# os20_oldenc.net
KiCad netlist of a schematic drawn in EAGLE
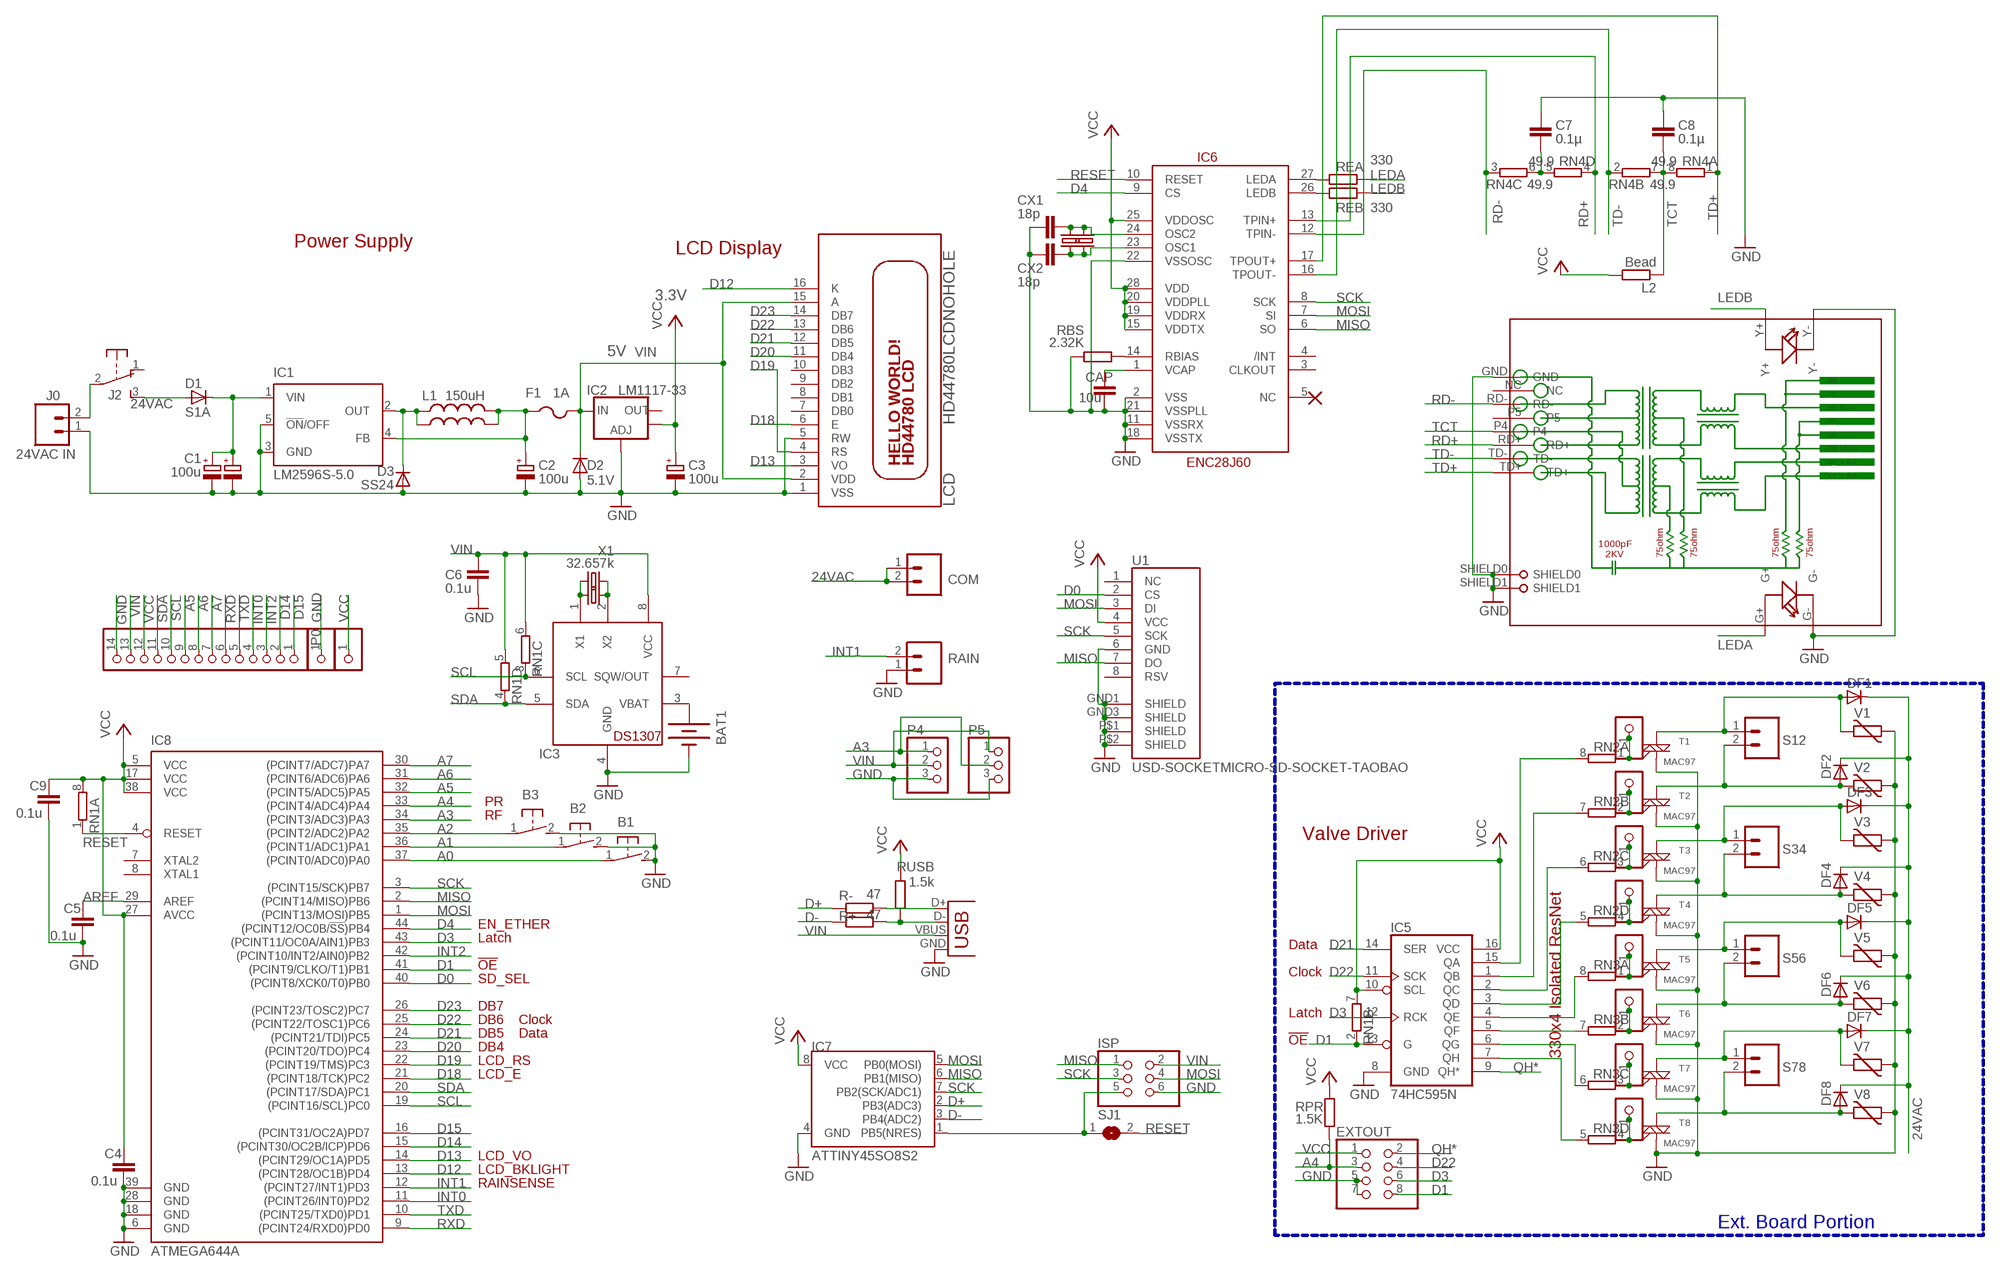
[diagram p0: schematic, sheet 1]

(export (version "E")
  (design (tool "Eeschema 10.0.6"))
  (components
    (comp (ref "B1")
      (value "31-XX")
      (footprint "eagle-import:B3F-31XX")
      (libsource (lib "eagle-import") (part "31-XX"))
    )
    (comp (ref "B2")
      (value "31-XX")
      (footprint "eagle-import:B3F-31XX")
      (libsource (lib "eagle-import") (part "31-XX"))
    )
    (comp (ref "B3")
      (value "31-XX")
      (footprint "eagle-import:B3F-31XX")
      (libsource (lib "eagle-import") (part "31-XX"))
    )
    (comp (ref "BAT1")
      (value "BATTERYBATTERY_12MM_SMT")
      (footprint "eagle-import:BATTCON_12MM_SMT")
      (libsource (lib "eagle-import") (part "BATTERYBATTERY_12MM_SMT"))
    )
    (comp (ref "C1")
      (value "100u")
      (footprint "eagle-import:E3,5-8")
      (libsource (lib "eagle-import") (part "CPOL-EUE3.5-8"))
    )
    (comp (ref "C1'")
      (value "100u")
      (footprint "eagle-import:PANASONIC_E")
      (libsource (lib "eagle-import") (part "CPOL-EUE"))
    )
    (comp (ref "C2")
      (value "100u")
      (footprint "eagle-import:PANASONIC_D")
      (libsource (lib "eagle-import") (part "CPOL-EUD"))
    )
    (comp (ref "C3")
      (value "100u")
      (footprint "eagle-import:PANASONIC_D")
      (libsource (lib "eagle-import") (part "CPOL-EUD"))
    )
    (comp (ref "C4")
      (value "0.1u")
      (footprint "eagle-import:C0805")
      (libsource (lib "eagle-import") (part "C-EUC0805"))
    )
    (comp (ref "C5")
      (value "0.1u")
      (footprint "eagle-import:C0805")
      (libsource (lib "eagle-import") (part "C-EUC0805"))
    )
    (comp (ref "C6")
      (value "0.1u")
      (footprint "eagle-import:C0805")
      (libsource (lib "eagle-import") (part "C-EUC0805"))
    )
    (comp (ref "C7")
      (value "0.1µ")
      (footprint "eagle-import:C0805")
      (libsource (lib "eagle-import") (part "resistor_C-EUC0805"))
    )
    (comp (ref "C8")
      (value "0.1µ")
      (footprint "eagle-import:C0805")
      (libsource (lib "eagle-import") (part "resistor_C-EUC0805"))
    )
    (comp (ref "C9")
      (value "0.1u")
      (footprint "eagle-import:C0805")
      (libsource (lib "eagle-import") (part "C-EUC0805"))
    )
    (comp (ref "CAP")
      (value "10u")
      (footprint "eagle-import:C0805")
      (libsource (lib "eagle-import") (part "resistor_C-EUC0805"))
    )
    (comp (ref "COM")
      (value "M025MM")
      (footprint "eagle-import:SCREWTERMINAL-5MM-2")
      (libsource (lib "eagle-import") (part "M025MM"))
    )
    (comp (ref "CX1")
      (value "18p")
      (footprint "eagle-import:C0805")
      (libsource (lib "eagle-import") (part "resistor_C-EUC0805"))
    )
    (comp (ref "CX2")
      (value "18p")
      (footprint "eagle-import:C0805")
      (libsource (lib "eagle-import") (part "resistor_C-EUC0805"))
    )
    (comp (ref "D1")
      (value "S1A")
      (footprint "eagle-import:DO-214AC")
      (libsource (lib "eagle-import") (part "DIODE-DO-214AC"))
    )
    (comp (ref "D2")
      (value "5.1V")
      (footprint "eagle-import:MINIMELF")
      (libsource (lib "eagle-import") (part "DIODE-MINIMELF"))
    )
    (comp (ref "D3")
      (value "SS24")
      (footprint "eagle-import:DO-214AC")
      (libsource (lib "eagle-import") (part "DIODE-DO-214AC"))
    )
    (comp (ref "DF1")
      (value "DIODE-D-2.5")
      (footprint "eagle-import:D-2.5")
      (libsource (lib "eagle-import") (part "DIODE-D-2.5"))
    )
    (comp (ref "DF2")
      (value "DIODE-D-2.5")
      (footprint "eagle-import:D-2.5")
      (libsource (lib "eagle-import") (part "DIODE-D-2.5"))
    )
    (comp (ref "DF3")
      (value "DIODE-D-2.5")
      (footprint "eagle-import:D-2.5")
      (libsource (lib "eagle-import") (part "DIODE-D-2.5"))
    )
    (comp (ref "DF4")
      (value "DIODE-D-2.5")
      (footprint "eagle-import:D-2.5")
      (libsource (lib "eagle-import") (part "DIODE-D-2.5"))
    )
    (comp (ref "DF5")
      (value "DIODE-D-2.5")
      (footprint "eagle-import:D-2.5")
      (libsource (lib "eagle-import") (part "DIODE-D-2.5"))
    )
    (comp (ref "DF6")
      (value "DIODE-D-2.5")
      (footprint "eagle-import:D-2.5")
      (libsource (lib "eagle-import") (part "DIODE-D-2.5"))
    )
    (comp (ref "DF7")
      (value "DIODE-D-2.5")
      (footprint "eagle-import:D-2.5")
      (libsource (lib "eagle-import") (part "DIODE-D-2.5"))
    )
    (comp (ref "DF8")
      (value "DIODE-D-2.5")
      (footprint "eagle-import:D-2.5")
      (libsource (lib "eagle-import") (part "DIODE-D-2.5"))
    )
    (comp (ref "EXTOUT")
      (value "PINHD-2X4")
      (footprint "eagle-import:2X04")
      (libsource (lib "eagle-import") (part "PINHD-2X4"))
    )
    (comp (ref "F1")
      (value "1A")
      (footprint "eagle-import:1812")
      (libsource (lib "eagle-import") (part "PTCFUSE-1812"))
    )
    (comp (ref "IC1")
      (value "LM2596S-5.0")
      (footprint "eagle-import:TO263-5")
      (fields (field (name "MF") "NATIONAL SEMICONDUCTOR") (field (name "MPN") "LM2596S-ADJ/NOPB"))
      (libsource (lib "eagle-import") (part "LM2596S"))
    )
    (comp (ref "IC2")
      (value "LM1117-33")
      (footprint "eagle-import:SOT223")
      (libsource (lib "eagle-import") (part "V_REG_LM1117SOT223"))
    )
    (comp (ref "IC3")
      (value "DS1307")
      (footprint "eagle-import:SO08")
      (libsource (lib "eagle-import") (part "DS1307SOIC"))
    )
    (comp (ref "IC5")
      (value "74HC595N")
      (footprint "eagle-import:SO16")
      (libsource (lib "eagle-import") (part "74595DLS"))
    )
    (comp (ref "IC6")
      (value "ENC28J60")
      (footprint "eagle-import:SOIC28WLONG")
      (libsource (lib "eagle-import") (part "ENC28J60SO28LONG"))
    )
    (comp (ref "IC7")
      (value "ATTINY45SO8S2")
      (footprint "eagle-import:SO8S2")
      (libsource (lib "eagle-import") (part "ATTINY45SO8S2"))
    )
    (comp (ref "IC8")
      (value "ATMEGA644A")
      (footprint "eagle-import:TQFP44")
      (fields (field (name "MPN") "ATMEGA644PV-10AU"))
      (libsource (lib "eagle-import") (part "ATMEGA644A"))
    )
    (comp (ref "ISP")
      (value "PINHD-2X3")
      (footprint "eagle-import:2X03")
      (libsource (lib "eagle-import") (part "PINHD-2X3"))
    )
    (comp (ref "J0")
      (value "24VAC IN")
      (footprint "eagle-import:SCREWTERMINAL-5MM-2")
      (libsource (lib "eagle-import") (part "M025MM"))
    )
    (comp (ref "J2")
      (value "EG1206")
      (footprint "eagle-import:EG1206")
      (libsource (lib "eagle-import") (part "EG1206"))
    )
    (comp (ref "JP2")
      (value "PINHD-1X1CB")
      (footprint "eagle-import:1X01-CLEANBIG")
      (libsource (lib "eagle-import") (part "PINHD-1X1CB"))
    )
    (comp (ref "JP3")
      (value "PINHD-1X1CB")
      (footprint "eagle-import:1X01-CLEANBIG")
      (libsource (lib "eagle-import") (part "PINHD-1X1CB"))
    )
    (comp (ref "JP4")
      (value "PINHD-1X1CB")
      (footprint "eagle-import:1X01-CLEANBIG")
      (libsource (lib "eagle-import") (part "PINHD-1X1CB"))
    )
    (comp (ref "JP5")
      (value "PINHD-1X1CB")
      (footprint "eagle-import:1X01-CLEANBIG")
      (libsource (lib "eagle-import") (part "PINHD-1X1CB"))
    )
    (comp (ref "JP6")
      (value "PINHD-1X1CB")
      (footprint "eagle-import:1X01-CLEANBIG")
      (libsource (lib "eagle-import") (part "PINHD-1X1CB"))
    )
    (comp (ref "JP7")
      (value "PINHD-1X1CB")
      (footprint "eagle-import:1X01-CLEANBIG")
      (libsource (lib "eagle-import") (part "PINHD-1X1CB"))
    )
    (comp (ref "JP8")
      (value "PINHD-1X1CB")
      (footprint "eagle-import:1X01-CLEANBIG")
      (libsource (lib "eagle-import") (part "PINHD-1X1CB"))
    )
    (comp (ref "JP9")
      (value "PINHD-1X1CB")
      (footprint "eagle-import:1X01-CLEANBIG")
      (libsource (lib "eagle-import") (part "PINHD-1X1CB"))
    )
    (comp (ref "L1")
      (value "150uH")
      (footprint "eagle-import:6000-XXXX-RC")
      (libsource (lib "eagle-import") (part "L-US6000-XXX-RC"))
    )
    (comp (ref "L1'")
      (value "220uH")
      (footprint "eagle-import:CDRH125")
      (libsource (lib "eagle-import") (part "INDUCTORPWR"))
    )
    (comp (ref "L2")
      (value "Bead")
      (footprint "eagle-import:R0805")
      (libsource (lib "eagle-import") (part "R-EU_R0805"))
    )
    (comp (ref "LCD")
      (value "HD44780LCDNOHOLE")
      (footprint "eagle-import:LCD1602A")
      (libsource (lib "eagle-import") (part "HD44780LCDNOHOLE"))
    )
    (comp (ref "P0")
      (value "PINHD-1X14-CB")
      (footprint "eagle-import:1X14-CB")
      (libsource (lib "eagle-import") (part "PINHD-1X14-CB"))
    )
    (comp (ref "P1")
      (value "PINHD-1X1CB")
      (footprint "eagle-import:1X01-CLEANBIG")
      (libsource (lib "eagle-import") (part "PINHD-1X1CB"))
    )
    (comp (ref "P2")
      (value "PINHD-1X1CB")
      (footprint "eagle-import:1X01-CLEANBIG")
      (libsource (lib "eagle-import") (part "PINHD-1X1CB"))
    )
    (comp (ref "P4")
      (value "PINHD-1X3")
      (footprint "eagle-import:1X03")
      (libsource (lib "eagle-import") (part "PINHD-1X3"))
    )
    (comp (ref "P5")
      (value "PINHD-1X3")
      (footprint "eagle-import:1X03")
      (libsource (lib "eagle-import") (part "PINHD-1X3"))
    )
    (comp (ref "R+")
      (value "47")
      (footprint "eagle-import:R0805")
      (libsource (lib "eagle-import") (part "R-EU_R0805"))
    )
    (comp (ref "R-")
      (value "47")
      (footprint "eagle-import:R0805")
      (libsource (lib "eagle-import") (part "R-EU_R0805"))
    )
    (comp (ref "RAIN")
      (value "M025MM")
      (footprint "eagle-import:SCREWTERMINAL-5MM-2")
      (libsource (lib "eagle-import") (part "M025MM"))
    )
    (comp (ref "RBS")
      (value "2.32K")
      (footprint "eagle-import:R0805")
      (libsource (lib "eagle-import") (part "R-EU_R0805"))
    )
    (comp (ref "REA")
      (value "330")
      (footprint "eagle-import:R0805")
      (libsource (lib "eagle-import") (part "R-EU_R0805"))
    )
    (comp (ref "REB")
      (value "330")
      (footprint "eagle-import:R0805")
      (libsource (lib "eagle-import") (part "R-EU_R0805"))
    )
    (comp (ref "RJ1")
      (value "HR911105A")
      (footprint "eagle-import:HR911105A")
      (libsource (lib "eagle-import") (part "HR911105A"))
    )
    (comp (ref "RN1")
      (value "4R-NEXB38V")
      (footprint "eagle-import:EXB38V")
      (libsource (lib "eagle-import") (part "4R-NEXB38V"))
    )
    (comp (ref "RN2")
      (value "4R-NEXB38V")
      (footprint "eagle-import:EXB38V")
      (libsource (lib "eagle-import") (part "4R-NEXB38V"))
    )
    (comp (ref "RN3")
      (value "4R-NEXB38V")
      (footprint "eagle-import:EXB38V")
      (libsource (lib "eagle-import") (part "4R-NEXB38V"))
    )
    (comp (ref "RN4")
      (value "49.9")
      (footprint "eagle-import:EXB38V")
      (libsource (lib "eagle-import") (part "4R-NEXB38V"))
    )
    (comp (ref "RPR")
      (value "1.5K")
      (footprint "eagle-import:R0805")
      (libsource (lib "eagle-import") (part "R-EU_R0805"))
    )
    (comp (ref "RUSB")
      (value "1.5k")
      (footprint "eagle-import:R0805")
      (libsource (lib "eagle-import") (part "R-EU_R0805"))
    )
    (comp (ref "S12")
      (value "M025MM")
      (footprint "eagle-import:SCREWTERMINAL-5MM-2")
      (libsource (lib "eagle-import") (part "M025MM"))
    )
    (comp (ref "S34")
      (value "M025MM")
      (footprint "eagle-import:SCREWTERMINAL-5MM-2")
      (libsource (lib "eagle-import") (part "M025MM"))
    )
    (comp (ref "S56")
      (value "M025MM")
      (footprint "eagle-import:SCREWTERMINAL-5MM-2")
      (libsource (lib "eagle-import") (part "M025MM"))
    )
    (comp (ref "S78")
      (value "M025MM")
      (footprint "eagle-import:SCREWTERMINAL-5MM-2")
      (libsource (lib "eagle-import") (part "M025MM"))
    )
    (comp (ref "SJ1") (value "SJ") (footprint "eagle-import:SJ") (libsource (lib "eagle-import") (part "SJ")))
    (comp (ref "T1")
      (value "MAC97")
      (footprint "eagle-import:SOT223")
      (libsource (lib "eagle-import") (part "MAC97SOT223"))
    )
    (comp (ref "T2")
      (value "MAC97")
      (footprint "eagle-import:SOT223")
      (libsource (lib "eagle-import") (part "MAC97SOT223"))
    )
    (comp (ref "T3")
      (value "MAC97")
      (footprint "eagle-import:SOT223")
      (libsource (lib "eagle-import") (part "MAC97SOT223"))
    )
    (comp (ref "T4")
      (value "MAC97")
      (footprint "eagle-import:SOT223")
      (libsource (lib "eagle-import") (part "MAC97SOT223"))
    )
    (comp (ref "T5")
      (value "MAC97")
      (footprint "eagle-import:SOT223")
      (libsource (lib "eagle-import") (part "MAC97SOT223"))
    )
    (comp (ref "T6")
      (value "MAC97")
      (footprint "eagle-import:SOT223")
      (libsource (lib "eagle-import") (part "MAC97SOT223"))
    )
    (comp (ref "T7")
      (value "MAC97")
      (footprint "eagle-import:SOT223")
      (libsource (lib "eagle-import") (part "MAC97SOT223"))
    )
    (comp (ref "T8")
      (value "MAC97")
      (footprint "eagle-import:SOT223")
      (libsource (lib "eagle-import") (part "MAC97SOT223"))
    )
    (comp (ref "U1")
      (value "USD-SOCKETMICRO-SD-SOCKET-TAOBAO")
      (footprint "eagle-import:MICRO-SD-SOCKET-TAOBAO")
      (libsource (lib "eagle-import") (part "USD-SOCKETMICRO-SD-SOCKET-TAOBAO"))
    )
    (comp (ref "USB")
      (value "USBPTH")
      (footprint "eagle-import:USB-B-PTH")
      (libsource (lib "eagle-import") (part "USBPTH"))
    )
    (comp (ref "V1")
      (value "MOV")
      (footprint "eagle-import:R-5")
      (libsource (lib "eagle-import") (part "VARISTOR-5"))
    )
    (comp (ref "V2")
      (value "MOV")
      (footprint "eagle-import:R-5")
      (libsource (lib "eagle-import") (part "VARISTOR-5"))
    )
    (comp (ref "V3")
      (value "MOV")
      (footprint "eagle-import:R-5")
      (libsource (lib "eagle-import") (part "VARISTOR-5"))
    )
    (comp (ref "V4")
      (value "MOV")
      (footprint "eagle-import:R-5")
      (libsource (lib "eagle-import") (part "VARISTOR-5"))
    )
    (comp (ref "V5")
      (value "MOV")
      (footprint "eagle-import:R-5")
      (libsource (lib "eagle-import") (part "VARISTOR-5"))
    )
    (comp (ref "V6")
      (value "MOV")
      (footprint "eagle-import:R-5")
      (libsource (lib "eagle-import") (part "VARISTOR-5"))
    )
    (comp (ref "V7")
      (value "MOV")
      (footprint "eagle-import:R-5")
      (libsource (lib "eagle-import") (part "VARISTOR-5"))
    )
    (comp (ref "V8")
      (value "MOV")
      (footprint "eagle-import:R-5")
      (libsource (lib "eagle-import") (part "VARISTOR-5"))
    )
    (comp (ref "X1")
      (value "32.657k")
      (footprint "eagle-import:TC26H")
      (libsource (lib "eagle-import") (part "crystal_CRYSTALTC26H"))
    )
    (comp (ref "X1'1")
      (value "32.657k")
      (footprint "eagle-import:MM20SS")
      (libsource (lib "eagle-import") (part "CRYSTALMM20SS"))
    )
    (comp (ref "X2")
      (value "25MHz")
      (footprint "eagle-import:CRYSTAL-SMD-10.5X4.8-2PIN")
      (libsource (lib "eagle-import") (part "CRYSTAL10.5X4.8"))
    )
    (comp (ref "X2'")
      (value "25MHz")
      (footprint "eagle-import:HC49US")
      (libsource (lib "eagle-import") (part "CRYSTALHC49US"))
    )
  )
  (nets
    (net (code "1") (name "/24VAC") (class "Default")
      (node (ref "COM") (pin "1") (pinfunction "1_1") (pintype "passive"))
      (node (ref "COM") (pin "2") (pinfunction "2_2") (pintype "passive"))
      (node (ref "D1") (pin "A") (pinfunction "A_A") (pintype "passive"))
      (node (ref "DF1") (pin "C") (pinfunction "C_C") (pintype "passive"))
      (node (ref "DF2") (pin "C") (pinfunction "C_C") (pintype "passive"))
      (node (ref "DF3") (pin "C") (pinfunction "C_C") (pintype "passive"))
      (node (ref "DF4") (pin "C") (pinfunction "C_C") (pintype "passive"))
      (node (ref "DF5") (pin "C") (pinfunction "C_C") (pintype "passive"))
      (node (ref "DF6") (pin "C") (pinfunction "C_C") (pintype "passive"))
      (node (ref "DF7") (pin "C") (pinfunction "C_C") (pintype "passive"))
      (node (ref "DF8") (pin "C") (pinfunction "C_C") (pintype "passive"))
      (node (ref "J2") (pin "3") (pinfunction "S_3") (pintype "passive"))
    )
    (net (code "2") (name "/A0") (class "Default")
      (node (ref "B1") (pin "1") (pinfunction "P_1") (pintype "passive"))
      (node (ref "IC8") (pin "37") (pinfunction "(PCINT0/ADC0)PA0_37") (pintype "bidirectional"))
    )
    (net (code "3") (name "/A1") (class "Default")
      (node (ref "B2") (pin "1") (pinfunction "P_1") (pintype "passive"))
      (node (ref "IC8") (pin "36") (pinfunction "(PCINT1/ADC1)PA1_36") (pintype "bidirectional"))
    )
    (net (code "4") (name "/A2") (class "Default")
      (node (ref "B3") (pin "1") (pinfunction "P_1") (pintype "passive"))
      (node (ref "IC8") (pin "35") (pinfunction "(PCINT2/ADC2)PA2_35") (pintype "bidirectional"))
    )
    (net (code "5") (name "/A3") (class "Default")
      (node (ref "IC8") (pin "34") (pinfunction "(PCINT3/ADC3)PA3_34") (pintype "bidirectional"))
      (node (ref "P4") (pin "1") (pinfunction "1_1") (pintype "passive"))
      (node (ref "P5") (pin "2") (pinfunction "2_2") (pintype "passive"))
    )
    (net (code "6") (name "/A4") (class "Default")
      (node (ref "EXTOUT") (pin "3") (pinfunction "3_3") (pintype "passive"))
      (node (ref "IC8") (pin "33") (pinfunction "(PCINT4/ADC4)PA4_33") (pintype "bidirectional"))
      (node (ref "RPR") (pin "1") (pinfunction "1_1") (pintype "passive"))
    )
    (net (code "7") (name "/A5") (class "Default")
      (node (ref "IC8") (pin "32") (pinfunction "(PCINT5/ADC5)PA5_32") (pintype "bidirectional"))
      (node (ref "P0") (pin "9") (pinfunction "9_9") (pintype "passive"))
    )
    (net (code "8") (name "/A6") (class "Default")
      (node (ref "IC8") (pin "31") (pinfunction "(PCINT6/ADC6)PA6_31") (pintype "bidirectional"))
      (node (ref "P0") (pin "8") (pinfunction "8_8") (pintype "passive"))
    )
    (net (code "9") (name "/A7") (class "Default")
      (node (ref "IC8") (pin "30") (pinfunction "(PCINT7/ADC7)PA7_30") (pintype "bidirectional"))
      (node (ref "P0") (pin "7") (pinfunction "7_7") (pintype "passive"))
    )
    (net (code "10") (name "/AREF") (class "Default")
      (node (ref "C5") (pin "1") (pinfunction "1_1") (pintype "passive"))
      (node (ref "IC8") (pin "29") (pinfunction "AREF_29") (pintype "passive"))
    )
    (net (code "11") (name "/D+") (class "Default")
      (node (ref "IC7") (pin "2") (pinfunction "PB3(ADC3)_2") (pintype "bidirectional"))
      (node (ref "R-") (pin "1") (pinfunction "1_1") (pintype "passive"))
    )
    (net (code "12") (name "/D-") (class "Default")
      (node (ref "IC7") (pin "3") (pinfunction "PB4(ADC2)_3") (pintype "bidirectional"))
      (node (ref "R+") (pin "1") (pinfunction "1_1") (pintype "passive"))
    )
    (net (code "13") (name "/D0") (class "Default")
      (node (ref "IC8") (pin "40") (pinfunction "(PCINT8/XCK0/T0)PB0_40") (pintype "bidirectional"))
      (node (ref "U1") (pin "2") (pinfunction "CS_2") (pintype "bidirectional"))
    )
    (net (code "14") (name "/D1") (class "Default")
      (node (ref "EXTOUT") (pin "8") (pinfunction "8_8") (pintype "passive"))
      (node (ref "IC5") (pin "13") (pinfunction "G_13") (pintype "input"))
      (node (ref "IC8") (pin "41") (pinfunction "(PCINT9/CLKO/T1)PB1_41") (pintype "bidirectional"))
      (node (ref "RN1") (pin "2") (pinfunction "1_2") (pintype "passive"))
    )
    (net (code "15") (name "/D3") (class "Default")
      (node (ref "EXTOUT") (pin "6") (pinfunction "6_6") (pintype "passive"))
      (node (ref "IC5") (pin "12") (pinfunction "RCK_12") (pintype "input"))
      (node (ref "IC8") (pin "43") (pinfunction "(PCINT11/OC0A/AIN1)PB3_43") (pintype "bidirectional"))
    )
    (net (code "16") (name "/D4") (class "Default")
      (node (ref "IC6") (pin "9") (pinfunction "CS_9") (pintype "bidirectional"))
      (node (ref "IC8") (pin "44") (pinfunction "(PCINT12/OC0B/~{SS})PB4_44") (pintype "bidirectional"))
    )
    (net (code "17") (name "/D12") (class "Default")
      (node (ref "IC8") (pin "13") (pinfunction "(PCINT28/OC1B)PD4_13") (pintype "bidirectional"))
      (node (ref "LCD") (pin "16") (pinfunction "K_16") (pintype "input"))
    )
    (net (code "18") (name "/D13") (class "Default")
      (node (ref "IC8") (pin "14") (pinfunction "(PCINT29/OC1A)PD5_14") (pintype "bidirectional"))
      (node (ref "LCD") (pin "3") (pinfunction "VO_3") (pintype "input"))
    )
    (net (code "19") (name "/D14") (class "Default")
      (node (ref "IC8") (pin "15") (pinfunction "(PCINT30/OC2B/ICP)PD6_15") (pintype "bidirectional"))
      (node (ref "P0") (pin "2") (pinfunction "2_2") (pintype "passive"))
    )
    (net (code "20") (name "/D15") (class "Default")
      (node (ref "IC8") (pin "16") (pinfunction "(PCINT31/OC2A)PD7_16") (pintype "bidirectional"))
      (node (ref "P0") (pin "1") (pinfunction "1_1") (pintype "passive"))
    )
    (net (code "21") (name "/D18") (class "Default")
      (node (ref "IC8") (pin "21") (pinfunction "(PCINT18/TCK)PC2_21") (pintype "output"))
      (node (ref "LCD") (pin "6") (pinfunction "E_6") (pintype "input"))
    )
    (net (code "22") (name "/D19") (class "Default")
      (node (ref "IC8") (pin "22") (pinfunction "(PCINT19/TMS)PC3_22") (pintype "output"))
      (node (ref "LCD") (pin "4") (pinfunction "RS_4") (pintype "input"))
    )
    (net (code "23") (name "/D20") (class "Default")
      (node (ref "IC8") (pin "23") (pinfunction "(PCINT20/TDO)PC4_23") (pintype "output"))
      (node (ref "LCD") (pin "11") (pinfunction "DB4_11") (pintype "bidirectional"))
    )
    (net (code "24") (name "/D21") (class "Default")
      (node (ref "IC5") (pin "14") (pinfunction "SER_14") (pintype "input"))
      (node (ref "IC8") (pin "24") (pinfunction "(PCINT21/TDI)PC5_24") (pintype "output"))
      (node (ref "LCD") (pin "12") (pinfunction "DB5_12") (pintype "bidirectional"))
    )
    (net (code "25") (name "/D22") (class "Default")
      (node (ref "EXTOUT") (pin "4") (pinfunction "4_4") (pintype "passive"))
      (node (ref "IC5") (pin "11") (pinfunction "SCK_11") (pintype "input"))
      (node (ref "IC8") (pin "25") (pinfunction "(PCINT22/TOSC1)PC6_25") (pintype "output"))
      (node (ref "LCD") (pin "13") (pinfunction "DB6_13") (pintype "bidirectional"))
    )
    (net (code "26") (name "/D23") (class "Default")
      (node (ref "IC8") (pin "26") (pinfunction "(PCINT23/TOSC2)PC7_26") (pintype "output"))
      (node (ref "LCD") (pin "14") (pinfunction "DB7_14") (pintype "bidirectional"))
    )
    (net (code "27") (name "/INT0") (class "Default")
      (node (ref "IC8") (pin "11") (pinfunction "(PCINT26/INT0)PD2_11") (pintype "bidirectional"))
      (node (ref "P0") (pin "4") (pinfunction "4_4") (pintype "passive"))
    )
    (net (code "28") (name "/INT1") (class "Default")
      (node (ref "IC8") (pin "12") (pinfunction "(PCINT27/INT1)PD3_12") (pintype "bidirectional"))
      (node (ref "RAIN") (pin "2") (pinfunction "2_2") (pintype "passive"))
    )
    (net (code "29") (name "/INT2") (class "Default")
      (node (ref "IC8") (pin "42") (pinfunction "(PCINT10/INT2/AIN0)PB2_42") (pintype "bidirectional"))
      (node (ref "P0") (pin "3") (pinfunction "3_3") (pintype "passive"))
    )
    (net (code "30") (name "/LEDA") (class "Default")
      (node (ref "REA") (pin "2") (pinfunction "2_2") (pintype "passive"))
      (node (ref "RJ1") (pin "G+") (pinfunction "G+_G+") (pintype "bidirectional"))
    )
    (net (code "31") (name "/LEDB") (class "Default")
      (node (ref "REB") (pin "2") (pinfunction "2_2") (pintype "passive"))
      (node (ref "RJ1") (pin "Y+") (pinfunction "Y+_Y+") (pintype "bidirectional"))
    )
    (net (code "32") (name "/MISO") (class "Default")
      (node (ref "IC6") (pin "6") (pinfunction "SO_6") (pintype "bidirectional"))
      (node (ref "IC7") (pin "6") (pinfunction "PB1(MISO)_6") (pintype "bidirectional"))
      (node (ref "IC8") (pin "2") (pinfunction "(PCINT14/MISO)PB6_2") (pintype "bidirectional"))
      (node (ref "ISP") (pin "1") (pinfunction "1_1") (pintype "passive"))
      (node (ref "U1") (pin "7") (pinfunction "DO_7") (pintype "bidirectional"))
    )
    (net (code "33") (name "/MOSI") (class "Default")
      (node (ref "IC6") (pin "7") (pinfunction "SI_7") (pintype "bidirectional"))
      (node (ref "IC7") (pin "5") (pinfunction "PB0(MOSI)_5") (pintype "bidirectional"))
      (node (ref "IC8") (pin "1") (pinfunction "(PCINT13/MOSI)PB5_1") (pintype "bidirectional"))
      (node (ref "ISP") (pin "4") (pinfunction "4_4") (pintype "passive"))
      (node (ref "U1") (pin "3") (pinfunction "DI_3") (pintype "bidirectional"))
    )
    (net (code "34") (name "/QH*") (class "Default")
      (node (ref "EXTOUT") (pin "2") (pinfunction "2_2") (pintype "passive"))
      (node (ref "IC5") (pin "9") (pinfunction "QH*_9") (pintype "tri_state"))
    )
    (net (code "35") (name "/RD+") (class "Default")
      (node (ref "IC6") (pin "13") (pinfunction "TPIN+_13") (pintype "bidirectional"))
      (node (ref "RJ1") (pin "RD+") (pinfunction "RD+_RD+") (pintype "bidirectional"))
      (node (ref "RN4") (pin "4") (pinfunction "1_4") (pintype "passive"))
    )
    (net (code "36") (name "/RD-") (class "Default")
      (node (ref "IC6") (pin "12") (pinfunction "TPIN-_12") (pintype "bidirectional"))
      (node (ref "RJ1") (pin "RD-") (pinfunction "RD-_RD-") (pintype "bidirectional"))
      (node (ref "RN4") (pin "3") (pinfunction "1_3") (pintype "passive"))
    )
    (net (code "37") (name "/RESET") (class "Default")
      (node (ref "IC6") (pin "10") (pinfunction "RESET_10") (pintype "bidirectional"))
      (node (ref "IC8") (pin "4") (pinfunction "RESET_4") (pintype "input"))
      (node (ref "RN1") (pin "1") (pinfunction "1_1") (pintype "passive"))
      (node (ref "SJ1") (pin "2") (pinfunction "2_2") (pintype "passive"))
    )
    (net (code "38") (name "/RXD") (class "Default")
      (node (ref "IC8") (pin "9") (pinfunction "(PCINT24/RXD0)PD0_9") (pintype "bidirectional"))
      (node (ref "P0") (pin "6") (pinfunction "6_6") (pintype "passive"))
    )
    (net (code "39") (name "/SCK") (class "Default")
      (node (ref "IC6") (pin "8") (pinfunction "SCK_8") (pintype "bidirectional"))
      (node (ref "IC7") (pin "7") (pinfunction "PB2(SCK/ADC1)_7") (pintype "bidirectional"))
      (node (ref "IC8") (pin "3") (pinfunction "(PCINT15/SCK)PB7_3") (pintype "bidirectional"))
      (node (ref "ISP") (pin "3") (pinfunction "3_3") (pintype "passive"))
      (node (ref "U1") (pin "5") (pinfunction "SCK_5") (pintype "bidirectional"))
    )
    (net (code "40") (name "/SCL") (class "Default")
      (node (ref "IC3") (pin "6") (pinfunction "SCL_6") (pintype "bidirectional"))
      (node (ref "IC8") (pin "19") (pinfunction "(PCINT16/SCL)PC0_19") (pintype "output"))
      (node (ref "P0") (pin "10") (pinfunction "10_10") (pintype "passive"))
      (node (ref "RN1") (pin "3") (pinfunction "1_3") (pintype "passive"))
    )
    (net (code "41") (name "/SDA") (class "Default")
      (node (ref "IC3") (pin "5") (pinfunction "SDA_5") (pintype "bidirectional"))
      (node (ref "IC8") (pin "20") (pinfunction "(PCINT17/SDA)PC1_20") (pintype "output"))
      (node (ref "P0") (pin "11") (pinfunction "11_11") (pintype "passive"))
      (node (ref "RN1") (pin "4") (pinfunction "1_4") (pintype "passive"))
    )
    (net (code "42") (name "/TCT") (class "Default")
      (node (ref "C8") (pin "2") (pinfunction "2_2") (pintype "passive"))
      (node (ref "L2") (pin "1") (pinfunction "1_1") (pintype "passive"))
      (node (ref "RJ1") (pin "P4") (pinfunction "P4_P4") (pintype "bidirectional"))
      (node (ref "RN4") (pin "7") (pinfunction "2_7") (pintype "passive"))
      (node (ref "RN4") (pin "8") (pinfunction "2_8") (pintype "passive"))
    )
    (net (code "43") (name "/TD+") (class "Default")
      (node (ref "IC6") (pin "17") (pinfunction "TPOUT+_17") (pintype "bidirectional"))
      (node (ref "RJ1") (pin "TD+") (pinfunction "TD+_TD+") (pintype "bidirectional"))
      (node (ref "RN4") (pin "1") (pinfunction "1_1") (pintype "passive"))
    )
    (net (code "44") (name "/TD-") (class "Default")
      (node (ref "IC6") (pin "16") (pinfunction "TPOUT-_16") (pintype "bidirectional"))
      (node (ref "RJ1") (pin "TD-") (pinfunction "TD-_TD-") (pintype "bidirectional"))
      (node (ref "RN4") (pin "2") (pinfunction "1_2") (pintype "passive"))
    )
    (net (code "45") (name "/TXD") (class "Default")
      (node (ref "IC8") (pin "10") (pinfunction "(PCINT25/TXD0)PD1_10") (pintype "bidirectional"))
      (node (ref "P0") (pin "5") (pinfunction "5_5") (pintype "passive"))
    )
    (net (code "46") (name "/VIN") (class "Default")
      (node (ref "C6") (pin "1") (pinfunction "1_1") (pintype "passive"))
      (node (ref "D2") (pin "C") (pinfunction "C_C") (pintype "passive"))
      (node (ref "F1") (pin "2") (pinfunction "2_2") (pintype "passive"))
      (node (ref "IC2") (pin "3") (pinfunction "IN_3") (pintype "input"))
      (node (ref "IC3") (pin "8") (pinfunction "VCC_8") (pintype "power_in"))
      (node (ref "ISP") (pin "2") (pinfunction "2_2") (pintype "passive"))
      (node (ref "LCD") (pin "15") (pinfunction "A_15") (pintype "input"))
      (node (ref "LCD") (pin "2") (pinfunction "VDD_2") (pintype "power_in"))
      (node (ref "P0") (pin "13") (pinfunction "13_13") (pintype "passive"))
      (node (ref "P4") (pin "2") (pinfunction "2_2") (pintype "passive"))
      (node (ref "P5") (pin "1") (pinfunction "1_1") (pintype "passive"))
      (node (ref "RN1") (pin "5") (pinfunction "2_5") (pintype "passive"))
      (node (ref "RN1") (pin "6") (pinfunction "2_6") (pintype "passive"))
      (node (ref "USB") (pin "VBUS") (pinfunction "VBUS_VBUS") (pintype "bidirectional"))
    )
    (net (code "47") (name "GND") (class "Default")
      (node (ref "B1") (pin "2") (pinfunction "S_2") (pintype "passive"))
      (node (ref "B2") (pin "2") (pinfunction "S_2") (pintype "passive"))
      (node (ref "B3") (pin "2") (pinfunction "S_2") (pintype "passive"))
      (node (ref "BAT1") (pin "P$1") (pinfunction "-_P$1") (pintype "power_in"))
      (node (ref "C1") (pin "-") (pinfunction "-_-") (pintype "passive"))
      (node (ref "C1'") (pin "-") (pinfunction "-_-") (pintype "passive"))
      (node (ref "C2") (pin "-") (pinfunction "-_-") (pintype "passive"))
      (node (ref "C3") (pin "-") (pinfunction "-_-") (pintype "passive"))
      (node (ref "C4") (pin "2") (pinfunction "2_2") (pintype "passive"))
      (node (ref "C5") (pin "2") (pinfunction "2_2") (pintype "passive"))
      (node (ref "C6") (pin "2") (pinfunction "2_2") (pintype "passive"))
      (node (ref "C7") (pin "1") (pinfunction "1_1") (pintype "passive"))
      (node (ref "C8") (pin "1") (pinfunction "1_1") (pintype "passive"))
      (node (ref "C9") (pin "2") (pinfunction "2_2") (pintype "passive"))
      (node (ref "CAP") (pin "2") (pinfunction "2_2") (pintype "passive"))
      (node (ref "CX1") (pin "2") (pinfunction "2_2") (pintype "passive"))
      (node (ref "CX2") (pin "2") (pinfunction "2_2") (pintype "passive"))
      (node (ref "D2") (pin "A") (pinfunction "A_A") (pintype "passive"))
      (node (ref "D3") (pin "A") (pinfunction "A_A") (pintype "passive"))
      (node (ref "EXTOUT") (pin "5") (pinfunction "5_5") (pintype "passive"))
      (node (ref "EXTOUT") (pin "7") (pinfunction "7_7") (pintype "passive"))
      (node (ref "IC1") (pin "3") (pinfunction "GND_3") (pintype "power_in"))
      (node (ref "IC1") (pin "5") (pinfunction "~{ON}/OFF_5") (pintype "input"))
      (node (ref "IC2") (pin "1") (pinfunction "ADJ_1") (pintype "input"))
      (node (ref "IC3") (pin "4") (pinfunction "GND_4") (pintype "power_in"))
      (node (ref "IC5") (pin "8") (pinfunction "GND_8") (pintype "power_in"))
      (node (ref "IC6") (pin "11") (pinfunction "VSSRX_11") (pintype "bidirectional"))
      (node (ref "IC6") (pin "18") (pinfunction "VSSTX_18") (pintype "bidirectional"))
      (node (ref "IC6") (pin "2") (pinfunction "VSS_2") (pintype "bidirectional"))
      (node (ref "IC6") (pin "21") (pinfunction "VSSPLL_21") (pintype "bidirectional"))
      (node (ref "IC6") (pin "22") (pinfunction "VSSOSC_22") (pintype "bidirectional"))
      (node (ref "IC7") (pin "4") (pinfunction "GND_4") (pintype "bidirectional"))
      (node (ref "IC8") (pin "18") (pinfunction "GND_18") (pintype "power_in"))
      (node (ref "IC8") (pin "28") (pinfunction "GND_28") (pintype "power_in"))
      (node (ref "IC8") (pin "39") (pinfunction "GND_39") (pintype "power_in"))
      (node (ref "IC8") (pin "6") (pinfunction "GND_6") (pintype "power_in"))
      (node (ref "ISP") (pin "6") (pinfunction "6_6") (pintype "passive"))
      (node (ref "J0") (pin "1") (pinfunction "1_1") (pintype "passive"))
      (node (ref "LCD") (pin "1") (pinfunction "VSS_1") (pintype "power_in"))
      (node (ref "LCD") (pin "5") (pinfunction "RW_5") (pintype "input"))
      (node (ref "P0") (pin "14") (pinfunction "14_14") (pintype "passive"))
      (node (ref "P2") (pin "1") (pinfunction "1_1") (pintype "passive"))
      (node (ref "P4") (pin "3") (pinfunction "3_3") (pintype "passive"))
      (node (ref "P5") (pin "3") (pinfunction "3_3") (pintype "passive"))
      (node (ref "RAIN") (pin "1") (pinfunction "1_1") (pintype "passive"))
      (node (ref "RBS") (pin "1") (pinfunction "1_1") (pintype "passive"))
      (node (ref "RJ1") (pin "G-") (pinfunction "G-_G-") (pintype "bidirectional"))
      (node (ref "RJ1") (pin "GND") (pinfunction "GND_GND") (pintype "bidirectional"))
      (node (ref "RJ1") (pin "SHIELD0") (pinfunction "SHIELD0_SHIELD0") (pintype "bidirectional"))
      (node (ref "RJ1") (pin "SHIELD1") (pinfunction "SHIELD1_SHIELD1") (pintype "bidirectional"))
      (node (ref "RJ1") (pin "Y-") (pinfunction "Y-_Y-") (pintype "bidirectional"))
      (node (ref "T1") (pin "1") (pinfunction "M1_1") (pintype "bidirectional"))
      (node (ref "T2") (pin "1") (pinfunction "M1_1") (pintype "bidirectional"))
      (node (ref "T3") (pin "1") (pinfunction "M1_1") (pintype "bidirectional"))
      (node (ref "T4") (pin "1") (pinfunction "M1_1") (pintype "bidirectional"))
      (node (ref "T5") (pin "1") (pinfunction "M1_1") (pintype "bidirectional"))
      (node (ref "T6") (pin "1") (pinfunction "M1_1") (pintype "bidirectional"))
      (node (ref "T7") (pin "1") (pinfunction "M1_1") (pintype "bidirectional"))
      (node (ref "T8") (pin "1") (pinfunction "M1_1") (pintype "bidirectional"))
      (node (ref "U1") (pin "6") (pinfunction "GND_6") (pintype "bidirectional"))
      (node (ref "U1") (pin "GND1") (pinfunction "SHIELD_GND1") (pintype "bidirectional"))
      (node (ref "U1") (pin "GND3") (pinfunction "SHIELD_GND3") (pintype "bidirectional"))
      (node (ref "U1") (pin "P$1") (pinfunction "SHIELD_P$1") (pintype "bidirectional"))
      (node (ref "U1") (pin "P$2") (pinfunction "SHIELD_P$2") (pintype "bidirectional"))
      (node (ref "USB") (pin "GND") (pinfunction "GND_GND") (pintype "bidirectional"))
      (node (ref "V1") (pin "1") (pinfunction "1_1") (pintype "passive"))
      (node (ref "V2") (pin "1") (pinfunction "1_1") (pintype "passive"))
      (node (ref "V3") (pin "1") (pinfunction "1_1") (pintype "passive"))
      (node (ref "V4") (pin "1") (pinfunction "1_1") (pintype "passive"))
      (node (ref "V5") (pin "1") (pinfunction "1_1") (pintype "passive"))
      (node (ref "V6") (pin "1") (pinfunction "1_1") (pintype "passive"))
      (node (ref "V7") (pin "1") (pinfunction "1_1") (pintype "passive"))
      (node (ref "V8") (pin "1") (pinfunction "1_1") (pintype "passive"))
    )
    (net (code "48") (name "Net-(BAT1-+)") (class "Default")
      (node (ref "BAT1") (pin "P$2") (pinfunction "+_P$2") (pintype "power_in"))
      (node (ref "IC3") (pin "3") (pinfunction "VBAT_3") (pintype "power_in"))
    )
    (net (code "49") (name "Net-(IC1-FB)") (class "Default")
      (node (ref "C2") (pin "+") (pinfunction "+_+") (pintype "passive"))
      (node (ref "F1") (pin "1") (pinfunction "1_1") (pintype "passive"))
      (node (ref "IC1") (pin "4") (pinfunction "FB_4") (pintype "input"))
      (node (ref "L1") (pin "2") (pinfunction "2_2") (pintype "passive"))
      (node (ref "L1'") (pin "2") (pinfunction "2_2") (pintype "passive"))
    )
    (net (code "50") (name "Net-(IC1-OUT)") (class "Default")
      (node (ref "D3") (pin "C") (pinfunction "C_C") (pintype "passive"))
      (node (ref "IC1") (pin "2") (pinfunction "OUT_2") (pintype "output"))
      (node (ref "L1") (pin "1") (pinfunction "1_1") (pintype "passive"))
      (node (ref "L1'") (pin "1") (pinfunction "1_1") (pintype "passive"))
    )
    (net (code "51") (name "Net-(IC1-VIN)") (class "Default")
      (node (ref "C1") (pin "+") (pinfunction "+_+") (pintype "passive"))
      (node (ref "C1'") (pin "+") (pinfunction "+_+") (pintype "passive"))
      (node (ref "D1") (pin "C") (pinfunction "C_C") (pintype "passive"))
      (node (ref "IC1") (pin "1") (pinfunction "VIN_1") (pintype "input"))
    )
    (net (code "52") (name "Net-(IC3-X1)") (class "Default")
      (node (ref "IC3") (pin "1") (pinfunction "X1_1") (pintype "passive"))
      (node (ref "X1") (pin "2") (pinfunction "2_2") (pintype "passive"))
      (node (ref "X1'1") (pin "1") (pinfunction "1_1") (pintype "passive"))
    )
    (net (code "53") (name "Net-(IC3-X2)") (class "Default")
      (node (ref "IC3") (pin "2") (pinfunction "X2_2") (pintype "passive"))
      (node (ref "X1") (pin "1") (pinfunction "1_1") (pintype "passive"))
      (node (ref "X1'1") (pin "4") (pinfunction "2_4") (pintype "passive"))
    )
    (net (code "54") (name "Net-(IC5-QA)") (class "Default")
      (node (ref "IC5") (pin "15") (pinfunction "QA_15") (pintype "tri_state"))
      (node (ref "RN2") (pin "8") (pinfunction "2_8") (pintype "passive"))
    )
    (net (code "55") (name "Net-(IC5-QB)") (class "Default")
      (node (ref "IC5") (pin "1") (pinfunction "QB_1") (pintype "tri_state"))
      (node (ref "RN2") (pin "7") (pinfunction "2_7") (pintype "passive"))
    )
    (net (code "56") (name "Net-(IC5-QC)") (class "Default")
      (node (ref "IC5") (pin "2") (pinfunction "QC_2") (pintype "tri_state"))
      (node (ref "RN2") (pin "6") (pinfunction "2_6") (pintype "passive"))
    )
    (net (code "57") (name "Net-(IC5-QD)") (class "Default")
      (node (ref "IC5") (pin "3") (pinfunction "QD_3") (pintype "tri_state"))
      (node (ref "RN2") (pin "5") (pinfunction "2_5") (pintype "passive"))
    )
    (net (code "58") (name "Net-(IC5-QE)") (class "Default")
      (node (ref "IC5") (pin "4") (pinfunction "QE_4") (pintype "tri_state"))
      (node (ref "RN3") (pin "8") (pinfunction "2_8") (pintype "passive"))
    )
    (net (code "59") (name "Net-(IC5-QF)") (class "Default")
      (node (ref "IC5") (pin "5") (pinfunction "QF_5") (pintype "tri_state"))
      (node (ref "RN3") (pin "7") (pinfunction "2_7") (pintype "passive"))
    )
    (net (code "60") (name "Net-(IC5-QG)") (class "Default")
      (node (ref "IC5") (pin "6") (pinfunction "QG_6") (pintype "tri_state"))
      (node (ref "RN3") (pin "6") (pinfunction "2_6") (pintype "passive"))
    )
    (net (code "61") (name "Net-(IC5-QH)") (class "Default")
      (node (ref "IC5") (pin "7") (pinfunction "QH_7") (pintype "tri_state"))
      (node (ref "RN3") (pin "5") (pinfunction "2_5") (pintype "passive"))
    )
    (net (code "62") (name "Net-(IC6-LEDA)") (class "Default")
      (node (ref "IC6") (pin "27") (pinfunction "LEDA_27") (pintype "bidirectional"))
      (node (ref "REA") (pin "1") (pinfunction "1_1") (pintype "passive"))
    )
    (net (code "63") (name "Net-(IC6-LEDB)") (class "Default")
      (node (ref "IC6") (pin "26") (pinfunction "LEDB_26") (pintype "bidirectional"))
      (node (ref "REB") (pin "1") (pinfunction "1_1") (pintype "passive"))
    )
    (net (code "64") (name "Net-(IC6-OSC1)") (class "Default")
      (node (ref "CX2") (pin "1") (pinfunction "1_1") (pintype "passive"))
      (node (ref "IC6") (pin "23") (pinfunction "OSC1_23") (pintype "bidirectional"))
      (node (ref "X2") (pin "P$1") (pinfunction "1_P$1") (pintype "passive"))
      (node (ref "X2'") (pin "1") (pinfunction "1_1") (pintype "passive"))
    )
    (net (code "65") (name "Net-(IC6-OSC2)") (class "Default")
      (node (ref "CX1") (pin "1") (pinfunction "1_1") (pintype "passive"))
      (node (ref "IC6") (pin "24") (pinfunction "OSC2_24") (pintype "bidirectional"))
      (node (ref "X2") (pin "P$2") (pinfunction "2_P$2") (pintype "passive"))
      (node (ref "X2'") (pin "2") (pinfunction "2_2") (pintype "passive"))
    )
    (net (code "66") (name "Net-(IC6-RBIAS)") (class "Default")
      (node (ref "IC6") (pin "14") (pinfunction "RBIAS_14") (pintype "bidirectional"))
      (node (ref "RBS") (pin "2") (pinfunction "2_2") (pintype "passive"))
    )
    (net (code "67") (name "Net-(IC6-VCAP)") (class "Default")
      (node (ref "CAP") (pin "1") (pinfunction "1_1") (pintype "passive"))
      (node (ref "IC6") (pin "1") (pinfunction "VCAP_1") (pintype "bidirectional"))
    )
    (net (code "68") (name "Net-(IC7-PB5(NRES))") (class "Default")
      (node (ref "IC7") (pin "1") (pinfunction "PB5(NRES)_1") (pintype "bidirectional"))
      (node (ref "ISP") (pin "5") (pinfunction "5_5") (pintype "passive"))
      (node (ref "SJ1") (pin "1") (pinfunction "1_1") (pintype "passive"))
    )
    (net (code "69") (name "Net-(J2-P)") (class "Default")
      (node (ref "J0") (pin "2") (pinfunction "2_2") (pintype "passive"))
      (node (ref "J2") (pin "2") (pinfunction "P_2") (pintype "passive"))
    )
    (net (code "70") (name "Net-(R+-Pad2)") (class "Default")
      (node (ref "R+") (pin "2") (pinfunction "2_2") (pintype "passive"))
      (node (ref "RUSB") (pin "1") (pinfunction "1_1") (pintype "passive"))
      (node (ref "USB") (pin "D-") (pinfunction "D-_D-") (pintype "bidirectional"))
    )
    (net (code "71") (name "Net-(R--Pad2)") (class "Default")
      (node (ref "R-") (pin "2") (pinfunction "2_2") (pintype "passive"))
      (node (ref "USB") (pin "D+") (pinfunction "D+_D+") (pintype "bidirectional"))
    )
    (net (code "72") (name "Net-(RN2B-1)") (class "Default")
      (node (ref "JP3") (pin "1") (pinfunction "1_1") (pintype "passive"))
      (node (ref "RN2") (pin "2") (pinfunction "1_2") (pintype "passive"))
      (node (ref "T2") (pin "3") (pinfunction "G_3") (pintype "bidirectional"))
    )
    (net (code "73") (name "Net-(RN2C-1)") (class "Default")
      (node (ref "JP4") (pin "1") (pinfunction "1_1") (pintype "passive"))
      (node (ref "RN2") (pin "3") (pinfunction "1_3") (pintype "passive"))
      (node (ref "T3") (pin "3") (pinfunction "G_3") (pintype "bidirectional"))
    )
    (net (code "74") (name "Net-(RN2D-1)") (class "Default")
      (node (ref "JP5") (pin "1") (pinfunction "1_1") (pintype "passive"))
      (node (ref "RN2") (pin "4") (pinfunction "1_4") (pintype "passive"))
      (node (ref "T4") (pin "3") (pinfunction "G_3") (pintype "bidirectional"))
    )
    (net (code "75") (name "Net-(RN3B-1)") (class "Default")
      (node (ref "JP7") (pin "1") (pinfunction "1_1") (pintype "passive"))
      (node (ref "RN3") (pin "2") (pinfunction "1_2") (pintype "passive"))
      (node (ref "T6") (pin "3") (pinfunction "G_3") (pintype "bidirectional"))
    )
    (net (code "76") (name "Net-(RN3C-1)") (class "Default")
      (node (ref "JP8") (pin "1") (pinfunction "1_1") (pintype "passive"))
      (node (ref "RN3") (pin "3") (pinfunction "1_3") (pintype "passive"))
      (node (ref "T7") (pin "3") (pinfunction "G_3") (pintype "bidirectional"))
    )
    (net (code "77") (name "Net-(RN3D-1)") (class "Default")
      (node (ref "JP9") (pin "1") (pinfunction "1_1") (pintype "passive"))
      (node (ref "RN3") (pin "4") (pinfunction "1_4") (pintype "passive"))
      (node (ref "T8") (pin "3") (pinfunction "G_3") (pintype "bidirectional"))
    )
    (net (code "78") (name "Net-(RN4C-2)") (class "Default")
      (node (ref "C7") (pin "2") (pinfunction "2_2") (pintype "passive"))
      (node (ref "RN4") (pin "5") (pinfunction "2_5") (pintype "passive"))
      (node (ref "RN4") (pin "6") (pinfunction "2_6") (pintype "passive"))
    )
    (net (code "79") (name "Net-(T1-G)") (class "Default")
      (node (ref "JP2") (pin "1") (pinfunction "1_1") (pintype "passive"))
      (node (ref "RN2") (pin "1") (pinfunction "1_1") (pintype "passive"))
      (node (ref "T1") (pin "3") (pinfunction "G_3") (pintype "bidirectional"))
    )
    (net (code "80") (name "Net-(T1-M2)") (class "Default")
      (node (ref "DF1") (pin "A") (pinfunction "A_A") (pintype "passive"))
      (node (ref "S12") (pin "1") (pinfunction "1_1") (pintype "passive"))
      (node (ref "T1") (pin "4") (pinfunction "M2_4") (pintype "bidirectional"))
      (node (ref "V1") (pin "2") (pinfunction "2_2") (pintype "passive"))
    )
    (net (code "81") (name "Net-(T2-M2)") (class "Default")
      (node (ref "DF2") (pin "A") (pinfunction "A_A") (pintype "passive"))
      (node (ref "S12") (pin "2") (pinfunction "2_2") (pintype "passive"))
      (node (ref "T2") (pin "4") (pinfunction "M2_4") (pintype "bidirectional"))
      (node (ref "V2") (pin "2") (pinfunction "2_2") (pintype "passive"))
    )
    (net (code "82") (name "Net-(T3-M2)") (class "Default")
      (node (ref "DF3") (pin "A") (pinfunction "A_A") (pintype "passive"))
      (node (ref "S34") (pin "1") (pinfunction "1_1") (pintype "passive"))
      (node (ref "T3") (pin "4") (pinfunction "M2_4") (pintype "bidirectional"))
      (node (ref "V3") (pin "2") (pinfunction "2_2") (pintype "passive"))
    )
    (net (code "83") (name "Net-(T4-M2)") (class "Default")
      (node (ref "DF4") (pin "A") (pinfunction "A_A") (pintype "passive"))
      (node (ref "S34") (pin "2") (pinfunction "2_2") (pintype "passive"))
      (node (ref "T4") (pin "4") (pinfunction "M2_4") (pintype "bidirectional"))
      (node (ref "V4") (pin "2") (pinfunction "2_2") (pintype "passive"))
    )
    (net (code "84") (name "Net-(T5-G)") (class "Default")
      (node (ref "JP6") (pin "1") (pinfunction "1_1") (pintype "passive"))
      (node (ref "RN3") (pin "1") (pinfunction "1_1") (pintype "passive"))
      (node (ref "T5") (pin "3") (pinfunction "G_3") (pintype "bidirectional"))
    )
    (net (code "85") (name "Net-(T5-M2)") (class "Default")
      (node (ref "DF5") (pin "A") (pinfunction "A_A") (pintype "passive"))
      (node (ref "S56") (pin "1") (pinfunction "1_1") (pintype "passive"))
      (node (ref "T5") (pin "4") (pinfunction "M2_4") (pintype "bidirectional"))
      (node (ref "V5") (pin "2") (pinfunction "2_2") (pintype "passive"))
    )
    (net (code "86") (name "Net-(T6-M2)") (class "Default")
      (node (ref "DF6") (pin "A") (pinfunction "A_A") (pintype "passive"))
      (node (ref "S56") (pin "2") (pinfunction "2_2") (pintype "passive"))
      (node (ref "T6") (pin "4") (pinfunction "M2_4") (pintype "bidirectional"))
      (node (ref "V6") (pin "2") (pinfunction "2_2") (pintype "passive"))
    )
    (net (code "87") (name "Net-(T7-M2)") (class "Default")
      (node (ref "DF7") (pin "A") (pinfunction "A_A") (pintype "passive"))
      (node (ref "S78") (pin "1") (pinfunction "1_1") (pintype "passive"))
      (node (ref "T7") (pin "4") (pinfunction "M2_4") (pintype "bidirectional"))
      (node (ref "V7") (pin "2") (pinfunction "2_2") (pintype "passive"))
    )
    (net (code "88") (name "Net-(T8-M2)") (class "Default")
      (node (ref "DF8") (pin "A") (pinfunction "A_A") (pintype "passive"))
      (node (ref "S78") (pin "2") (pinfunction "2_2") (pintype "passive"))
      (node (ref "T8") (pin "4") (pinfunction "M2_4") (pintype "bidirectional"))
      (node (ref "V8") (pin "2") (pinfunction "2_2") (pintype "passive"))
    )
    (net (code "89") (name "VCC") (class "Default")
      (node (ref "C3") (pin "+") (pinfunction "+_+") (pintype "passive"))
      (node (ref "C4") (pin "1") (pinfunction "1_1") (pintype "passive"))
      (node (ref "C9") (pin "1") (pinfunction "1_1") (pintype "passive"))
      (node (ref "EXTOUT") (pin "1") (pinfunction "1_1") (pintype "passive"))
      (node (ref "IC2") (pin "4") (pinfunction "OUT_4") (pintype "bidirectional"))
      (node (ref "IC5") (pin "10") (pinfunction "SCL_10") (pintype "input"))
      (node (ref "IC5") (pin "16") (pinfunction "VCC_16") (pintype "power_in"))
      (node (ref "IC6") (pin "15") (pinfunction "VDDTX_15") (pintype "bidirectional"))
      (node (ref "IC6") (pin "19") (pinfunction "VDDRX_19") (pintype "bidirectional"))
      (node (ref "IC6") (pin "20") (pinfunction "VDDPLL_20") (pintype "bidirectional"))
      (node (ref "IC6") (pin "25") (pinfunction "VDDOSC_25") (pintype "bidirectional"))
      (node (ref "IC6") (pin "28") (pinfunction "VDD_28") (pintype "bidirectional"))
      (node (ref "IC7") (pin "8") (pinfunction "VCC_8") (pintype "bidirectional"))
      (node (ref "IC8") (pin "17") (pinfunction "VCC_17") (pintype "power_in"))
      (node (ref "IC8") (pin "27") (pinfunction "AVCC_27") (pintype "power_in"))
      (node (ref "IC8") (pin "38") (pinfunction "VCC_38") (pintype "power_in"))
      (node (ref "IC8") (pin "5") (pinfunction "VCC_5") (pintype "power_in"))
      (node (ref "L2") (pin "2") (pinfunction "2_2") (pintype "passive"))
      (node (ref "P0") (pin "12") (pinfunction "12_12") (pintype "passive"))
      (node (ref "P1") (pin "1") (pinfunction "1_1") (pintype "passive"))
      (node (ref "RN1") (pin "7") (pinfunction "2_7") (pintype "passive"))
      (node (ref "RN1") (pin "8") (pinfunction "2_8") (pintype "passive"))
      (node (ref "RPR") (pin "2") (pinfunction "2_2") (pintype "passive"))
      (node (ref "RUSB") (pin "2") (pinfunction "2_2") (pintype "passive"))
      (node (ref "U1") (pin "4") (pinfunction "VCC_4") (pintype "bidirectional"))
    )
    (net (code "90") (name "unconnected-(IC2-OUT-Pad2)") (class "Default")
      (node (ref "IC2") (pin "2") (pinfunction "OUT_2") (pintype "bidirectional"))
    )
    (net (code "91") (name "unconnected-(IC3-SQW{slash}OUT-Pad7)") (class "Default")
      (node (ref "IC3") (pin "7") (pinfunction "SQW/OUT_7") (pintype "bidirectional"))
    )
    (net (code "92") (name "unconnected-(IC6-CLKOUT-Pad3)") (class "Default")
      (node (ref "IC6") (pin "3") (pinfunction "CLKOUT_3") (pintype "bidirectional"))
    )
    (net (code "93") (name "unconnected-(IC6-NC-Pad5)") (class "Default")
      (node (ref "IC6") (pin "5") (pinfunction "NC_5") (pintype "bidirectional"))
    )
    (net (code "94") (name "unconnected-(IC6-{slash}INT-Pad4)") (class "Default")
      (node (ref "IC6") (pin "4") (pinfunction "/INT_4") (pintype "bidirectional"))
    )
    (net (code "95") (name "unconnected-(IC8-XTAL1-Pad8)") (class "Default")
      (node (ref "IC8") (pin "8") (pinfunction "XTAL1_8") (pintype "bidirectional"))
    )
    (net (code "96") (name "unconnected-(IC8-XTAL2-Pad7)") (class "Default")
      (node (ref "IC8") (pin "7") (pinfunction "XTAL2_7") (pintype "bidirectional"))
    )
    (net (code "97") (name "unconnected-(J2-O-Pad1)") (class "Default")
      (node (ref "J2") (pin "1") (pinfunction "O_1") (pintype "passive"))
    )
    (net (code "98") (name "unconnected-(LCD-DB0-Pad7)") (class "Default")
      (node (ref "LCD") (pin "7") (pinfunction "DB0_7") (pintype "bidirectional"))
    )
    (net (code "99") (name "unconnected-(LCD-DB1-Pad8)") (class "Default")
      (node (ref "LCD") (pin "8") (pinfunction "DB1_8") (pintype "bidirectional"))
    )
    (net (code "100") (name "unconnected-(LCD-DB2-Pad9)") (class "Default")
      (node (ref "LCD") (pin "9") (pinfunction "DB2_9") (pintype "bidirectional"))
    )
    (net (code "101") (name "unconnected-(LCD-DB3-Pad10)") (class "Default")
      (node (ref "LCD") (pin "10") (pinfunction "DB3_10") (pintype "bidirectional"))
    )
    (net (code "102") (name "unconnected-(RJ1-PadNC)") (class "Default")
      (node (ref "RJ1") (pin "NC") (pinfunction "NC_NC") (pintype "bidirectional"))
    )
    (net (code "103") (name "unconnected-(RJ1-PadP5)") (class "Default")
      (node (ref "RJ1") (pin "P5") (pinfunction "P5_P5") (pintype "bidirectional"))
    )
    (net (code "104") (name "unconnected-(U1-NC-Pad1)") (class "Default")
      (node (ref "U1") (pin "1") (pinfunction "NC_1") (pintype "bidirectional"))
    )
    (net (code "105") (name "unconnected-(U1-RSV-Pad8)") (class "Default")
      (node (ref "U1") (pin "8") (pinfunction "RSV_8") (pintype "bidirectional"))
    )
  )
)
